# bat_connectors.net
KiCad netlist of a schematic drawn in Altium Designer
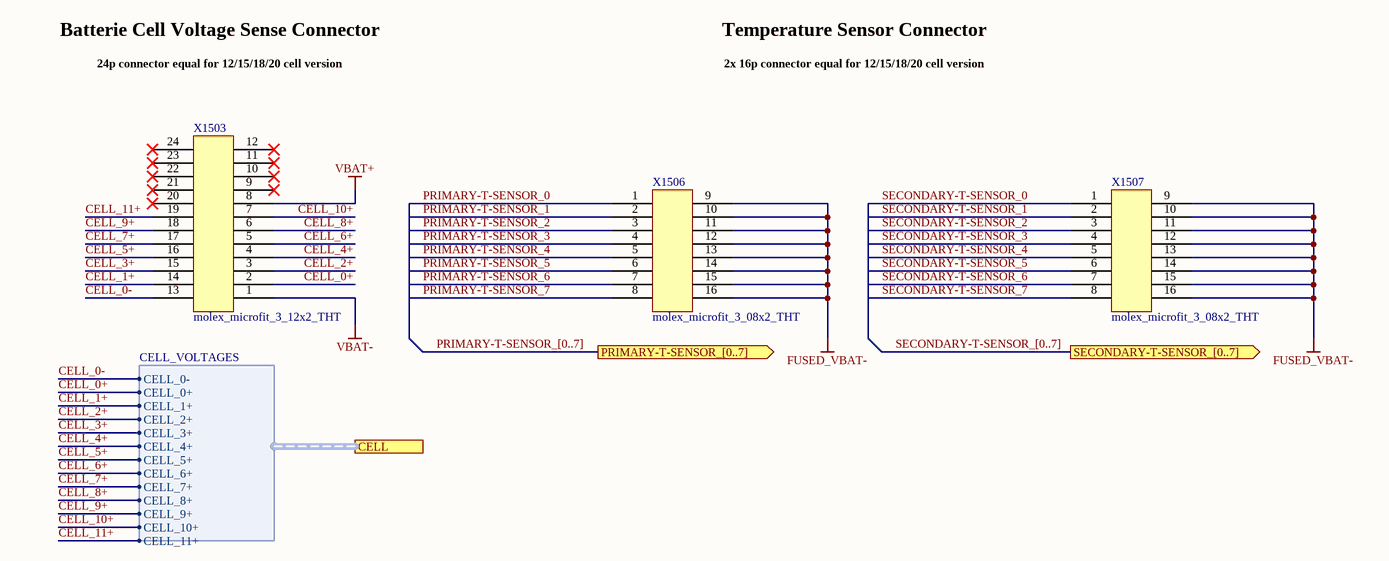
[diagram p0: bat_connectors.SchDoc]

(export (version "E")
  (design (tool "Eeschema 10.0.6"))
  (components
    (comp (ref "X1503")
      (value "molex_microfit_3_12x2_THT")
      (footprint "MOLEX_MICROFIT_12x2_THT")
      (fields (field (name "MANUFACTURER") "Molex"))
      (libsource (lib "OE750") (part "X12x2"))
    )
    (comp (ref "X1506")
      (value "molex_microfit_3_08x2_THT")
      (footprint "MOLEX_MICROFIT_08x2_THT")
      (fields (field (name "MANUFACTURER") "Molex"))
      (libsource (lib "OE750") (part "X8x2"))
    )
    (comp (ref "X1507")
      (value "molex_microfit_3_08x2_THT")
      (footprint "MOLEX_MICROFIT_08x2_THT")
      (fields (field (name "MANUFACTURER") "Molex"))
      (libsource (lib "OE750") (part "X8x2"))
    )
  )
  (nets
    (net (code "2") (name "/CELL_0+") (class "Default") (node (ref "X1503") (pin "2") (pintype "passive")))
    (net (code "3") (name "/CELL_0-") (class "Default") (node (ref "X1503") (pin "13") (pintype "passive")))
    (net (code "4") (name "/CELL_1+") (class "Default") (node (ref "X1503") (pin "14") (pintype "passive")))
    (net (code "5") (name "/CELL_2+") (class "Default") (node (ref "X1503") (pin "3") (pintype "passive")))
    (net (code "6") (name "/CELL_3+") (class "Default") (node (ref "X1503") (pin "15") (pintype "passive")))
    (net (code "7") (name "/CELL_4+") (class "Default") (node (ref "X1503") (pin "4") (pintype "passive")))
    (net (code "8") (name "/CELL_5+") (class "Default") (node (ref "X1503") (pin "16") (pintype "passive")))
    (net (code "9") (name "/CELL_6+") (class "Default") (node (ref "X1503") (pin "5") (pintype "passive")))
    (net (code "10") (name "/CELL_7+") (class "Default") (node (ref "X1503") (pin "17") (pintype "passive")))
    (net (code "11") (name "/CELL_8+") (class "Default") (node (ref "X1503") (pin "6") (pintype "passive")))
    (net (code "12") (name "/CELL_9+") (class "Default") (node (ref "X1503") (pin "18") (pintype "passive")))
    (net (code "13") (name "/CELL_10+") (class "Default") (node (ref "X1503") (pin "7") (pintype "passive")))
    (net (code "14") (name "/CELL_11+") (class "Default") (node (ref "X1503") (pin "19") (pintype "passive")))
    (net (code "15") (name "/PRIMARY-T-SENSOR_0") (class "Default")
      (node (ref "X1506") (pin "1") (pintype "passive"))
    )
    (net (code "16") (name "/PRIMARY-T-SENSOR_1") (class "Default")
      (node (ref "X1506") (pin "2") (pintype "passive"))
    )
    (net (code "17") (name "/PRIMARY-T-SENSOR_2") (class "Default")
      (node (ref "X1506") (pin "3") (pintype "passive"))
    )
    (net (code "18") (name "/PRIMARY-T-SENSOR_3") (class "Default")
      (node (ref "X1506") (pin "4") (pintype "passive"))
    )
    (net (code "19") (name "/PRIMARY-T-SENSOR_4") (class "Default")
      (node (ref "X1506") (pin "5") (pintype "passive"))
    )
    (net (code "20") (name "/PRIMARY-T-SENSOR_5") (class "Default")
      (node (ref "X1506") (pin "6") (pintype "passive"))
    )
    (net (code "21") (name "/PRIMARY-T-SENSOR_6") (class "Default")
      (node (ref "X1506") (pin "7") (pintype "passive"))
    )
    (net (code "22") (name "/PRIMARY-T-SENSOR_7") (class "Default")
      (node (ref "X1506") (pin "8") (pintype "passive"))
    )
    (net (code "24") (name "/SECONDARY-T-SENSOR_0") (class "Default")
      (node (ref "X1507") (pin "1") (pintype "passive"))
    )
    (net (code "25") (name "/SECONDARY-T-SENSOR_1") (class "Default")
      (node (ref "X1507") (pin "2") (pintype "passive"))
    )
    (net (code "26") (name "/SECONDARY-T-SENSOR_2") (class "Default")
      (node (ref "X1507") (pin "3") (pintype "passive"))
    )
    (net (code "27") (name "/SECONDARY-T-SENSOR_3") (class "Default")
      (node (ref "X1507") (pin "4") (pintype "passive"))
    )
    (net (code "28") (name "/SECONDARY-T-SENSOR_4") (class "Default")
      (node (ref "X1507") (pin "5") (pintype "passive"))
    )
    (net (code "29") (name "/SECONDARY-T-SENSOR_5") (class "Default")
      (node (ref "X1507") (pin "6") (pintype "passive"))
    )
    (net (code "30") (name "/SECONDARY-T-SENSOR_6") (class "Default")
      (node (ref "X1507") (pin "7") (pintype "passive"))
    )
    (net (code "31") (name "/SECONDARY-T-SENSOR_7") (class "Default")
      (node (ref "X1507") (pin "8") (pintype "passive"))
    )
    (net (code "34") (name "FUSED_VBAT-") (class "Default")
      (node (ref "X1506") (pin "10") (pintype "passive"))
      (node (ref "X1506") (pin "11") (pintype "passive"))
      (node (ref "X1506") (pin "12") (pintype "passive"))
      (node (ref "X1506") (pin "13") (pintype "passive"))
      (node (ref "X1506") (pin "14") (pintype "passive"))
      (node (ref "X1506") (pin "15") (pintype "passive"))
      (node (ref "X1506") (pin "16") (pintype "passive"))
      (node (ref "X1506") (pin "9") (pintype "passive"))
      (node (ref "X1507") (pin "10") (pintype "passive"))
      (node (ref "X1507") (pin "11") (pintype "passive"))
      (node (ref "X1507") (pin "12") (pintype "passive"))
      (node (ref "X1507") (pin "13") (pintype "passive"))
      (node (ref "X1507") (pin "14") (pintype "passive"))
      (node (ref "X1507") (pin "15") (pintype "passive"))
      (node (ref "X1507") (pin "16") (pintype "passive"))
      (node (ref "X1507") (pin "9") (pintype "passive"))
    )
    (net (code "35") (name "VBAT+") (class "Default") (node (ref "X1503") (pin "8") (pintype "passive")))
    (net (code "36") (name "VBAT-") (class "Default") (node (ref "X1503") (pin "1") (pintype "passive")))
    (net (code "37") (name "unconnected-(X1503-Pad9)") (class "Default")
      (node (ref "X1503") (pin "9") (pintype "passive+no_connect"))
    )
    (net (code "38") (name "unconnected-(X1503-Pad10)") (class "Default")
      (node (ref "X1503") (pin "10") (pintype "passive+no_connect"))
    )
    (net (code "39") (name "unconnected-(X1503-Pad11)") (class "Default")
      (node (ref "X1503") (pin "11") (pintype "passive+no_connect"))
    )
    (net (code "40") (name "unconnected-(X1503-Pad12)") (class "Default")
      (node (ref "X1503") (pin "12") (pintype "passive+no_connect"))
    )
    (net (code "41") (name "unconnected-(X1503-Pad20)") (class "Default")
      (node (ref "X1503") (pin "20") (pintype "passive+no_connect"))
    )
    (net (code "42") (name "unconnected-(X1503-Pad21)") (class "Default")
      (node (ref "X1503") (pin "21") (pintype "passive+no_connect"))
    )
    (net (code "43") (name "unconnected-(X1503-Pad22)") (class "Default")
      (node (ref "X1503") (pin "22") (pintype "passive+no_connect"))
    )
    (net (code "44") (name "unconnected-(X1503-Pad23)") (class "Default")
      (node (ref "X1503") (pin "23") (pintype "passive+no_connect"))
    )
    (net (code "45") (name "unconnected-(X1503-Pad24)") (class "Default")
      (node (ref "X1503") (pin "24") (pintype "passive+no_connect"))
    )
  )
)
